# PowerDistribution.net
KiCad netlist of a schematic drawn in Altium Designer
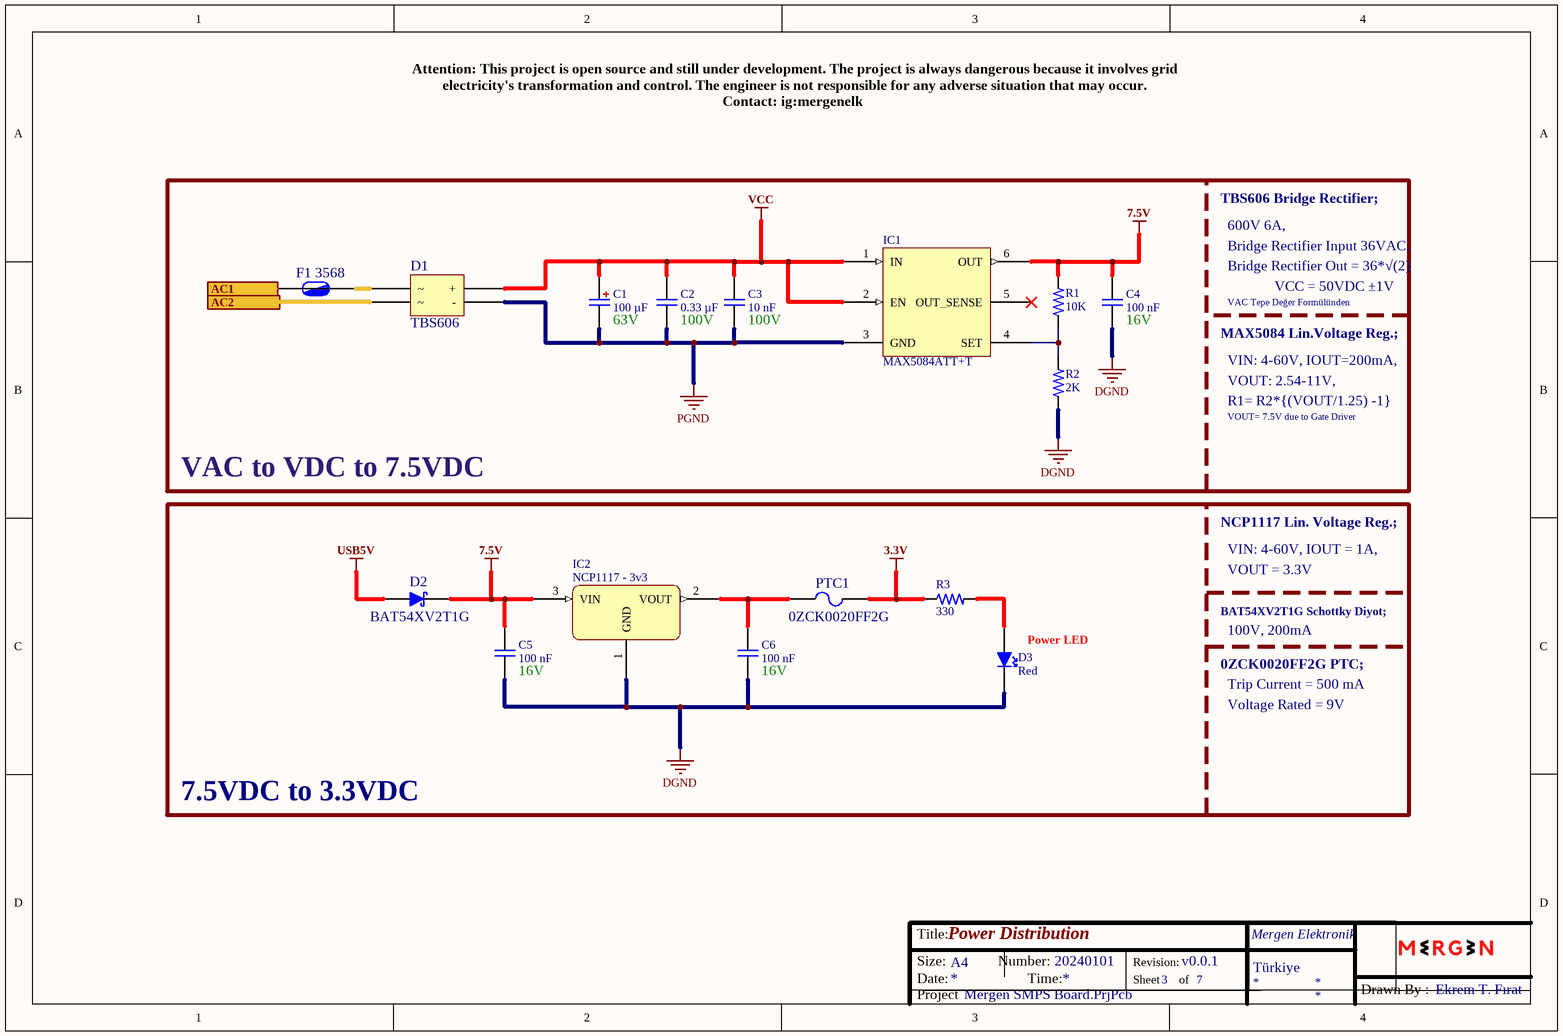
[diagram p0: PowerDistribution.SchDoc]

(export (version "E")
  (design (tool "Eeschema 10.0.6"))
  (components
    (comp (ref "C1")
      (value "100 µF")
      (footprint "MergenElektronik_Capacitors_AluminumElectrolytics_SMDs_10x10.5mm")
      (description "Mergen Elektronik - Capacitors - Aluminum Electrolytics - SMDs - UUX1J101MNL1GS")
      (fields
        (field (name "MANUFACTURER") "Nichicon")
        (field (name "TOLERANCE") "±20%")
        (field (name "VOLTAGE RATED") "63V")
      )
      (libsource (lib "MergenElektronik_Capacitors_AluminumElectrolytics_SMDs") (part "MergenElektronik_Capacitors_AluminumElectrolytics_SMDs_UUX1J101MNL1GS"))
    )
    (comp (ref "C2")
      (value "0.33 µF")
      (footprint "MergenElektronik_Capacitors_Ceramics_SMDs_1206_S_NS")
      (description "Mergen Elektronik - Capacitors - Ceramics - SMDs - 1206 - 0.33 µF - 100V")
      (fields
        (field (name "MANUFACTURER") "TDK Corporation")
        (field (name "TOLERANCE") "±10%")
        (field (name "VOLTAGE RATED") "100V")
      )
      (libsource (lib "MergenElektronik_Capacitors_Ceramics_SMDs") (part "MergenElektronik_Capacitors_Ceramic_SMDs_0.33µF_100V"))
    )
    (comp (ref "C3")
      (value "10 nF")
      (footprint "MergenElektronik_Capacitors_Ceramics_SMDs_0603_S_NS")
      (description "Mergen Elektronik - Capacitors - Ceramics - SMDs - 0603 - 10 nF - 100V")
      (fields
        (field (name "MANUFACTURER") "Murata Electronics")
        (field (name "TOLERANCE") "±10%")
        (field (name "VOLTAGE RATED") "100V")
      )
      (libsource (lib "MergenElektronik_Capacitors_Ceramics_SMDs") (part "MergenElektronik_Capacitors_Ceramic_SMDs_10nF_100V"))
    )
    (comp (ref "C4")
      (value "100 nF")
      (footprint "MergenElektronik_Capacitors_Ceramics_SMDs_0603_S_NS")
      (description "Mergen Elektronik - Capacitors - Ceramics - SMDs - 0603 - 100 nF - 16V")
      (fields
        (field (name "MANUFACTURER") "Samsung")
        (field (name "TOLERANCE") "±10%")
        (field (name "VOLTAGE RATED") "16V")
      )
      (libsource (lib "MergenElektronik_Capacitors_Ceramics_SMDs") (part "MergenElektronik_Capacitors_Ceramic_SMDs_100nF_16V"))
    )
    (comp (ref "C5")
      (value "100 nF")
      (footprint "MergenElektronik_Capacitors_Ceramics_SMDs_0603_S_NS")
      (description "Mergen Elektronik - Capacitors - Ceramics - SMDs - 0603 - 100 nF - 16V")
      (fields
        (field (name "MANUFACTURER") "Samsung")
        (field (name "TOLERANCE") "±10%")
        (field (name "VOLTAGE RATED") "16V")
      )
      (libsource (lib "MergenElektronik_Capacitors_Ceramics_SMDs") (part "MergenElektronik_Capacitors_Ceramic_SMDs_100nF_16V"))
    )
    (comp (ref "C6")
      (value "100 nF")
      (footprint "MergenElektronik_Capacitors_Ceramics_SMDs_0603_S_NS")
      (description "Mergen Elektronik - Capacitors - Ceramics - SMDs - 0603 - 100 nF - 16V")
      (fields
        (field (name "MANUFACTURER") "Samsung")
        (field (name "TOLERANCE") "±10%")
        (field (name "VOLTAGE RATED") "16V")
      )
      (libsource (lib "MergenElektronik_Capacitors_Ceramics_SMDs") (part "MergenElektronik_Capacitors_Ceramic_SMDs_100nF_16V"))
    )
    (comp (ref "D1")
      (value "TBS606")
      (footprint "MergenElektronik_Diodes_BridgeRectifiers_TBS606")
      (description "Mergen Elektronik - Diodes - Bridge Rectifiers - TBS606")
      (fields (field (name "MANUFACTURER") "Taiwan Semiconductor Corporation"))
      (libsource (lib "MergenElektronik_Diodes_BridgeRectifiers") (part "MergenElektronik_Diodes_BridgeRectifiers_TBS606"))
    )
    (comp (ref "D2")
      (value "BAT54XV2T1G")
      (footprint "MergenElektronik_Diodes_SchottkyDiodes_SOD-523")
      (description "Mergen Elektronik - Diodes - Schottky Diodes - BAT54XV2T1G")
      (fields (field (name "MANUFACTURER") "onsemi"))
      (libsource (lib "MergenElektronik_Diodes_SchottkyDiodes") (part "MergenElektronik_Diodes_SchottkyDiodes_BAT54XV2T1G"))
    )
    (comp (ref "D3")
      (value "Red")
      (footprint "MergenElektronik_Leds_SMDs_0603_S_NS")
      (description "Mergen Elektronik - Leds - SMDs - Red - 0603")
      (fields (field (name "MANUFACTURER") "Würth Elektronik"))
      (libsource (lib "MergenElektronik_Leds_SMDs") (part "MergenElektronik_LEDs_SMDs_Red_0603"))
    )
    (comp (ref "F1")
      (value "3568")
      (footprint "MergenElektronik_FuseHolders_BladeType_3568")
      (description "Mergen Elektronik - Fuse Holder - Blade Type - 3568")
      (fields (field (name "MANUFACTURER") "Keystone"))
      (libsource (lib "MergenElektronik_FuseHolders_BladeType") (part "MergenElektronik_FuseHolders_BladeType_3568"))
    )
    (comp (ref "IC1")
      (value "MAX5084ATT+T")
      (footprint "MergenElektronik_Regulators_Linears_6-TDFN")
      (description "Mergen Elektronik - Regulators - Linears - MAX5084ATT+T")
      (fields (field (name "MANUFACTURER") "Analog Devices Inc./Maxim Integrated"))
      (libsource (lib "MergenElektronik_Regulators_Linears") (part "MergenElektronik_Regulators_Linears_MAX5084ATT+T"))
    )
    (comp (ref "IC2")
      (value "NCP1117 - 3v3")
      (footprint "MergenElektronik_Regulators_Linears_SOT223")
      (description "Mergen Elektronik - Regulators - Linears - NCP1117ST33T3G")
      (fields (field (name "MANUFACTURER") "onsemi"))
      (libsource (lib "MergenElektronik_Regulators_Linears") (part "MergenElektronik_Regulators_Linears_NCP1117ST33T3G"))
    )
    (comp (ref "PTC1")
      (value "0ZCK0020FF2G")
      (footprint "MergenElektronik_CircuitProtections_PTCs_0603_S_NS")
      (description "Mergen Elektronik - Circuit Protections - PTCs - 0ZCK0020FF2G")
      (fields (field (name "MANUFACTURER") "Bel Fuse"))
      (libsource (lib "MergenElektronik_CircuitProtections_PTCs") (part "MergenElektronik_CircuitProtections_PTCs_0ZCK0020FF2G"))
    )
    (comp (ref "R1")
      (value "10K")
      (footprint "MergenElektronik_Resistors_ChipResistors_0603_S_NS")
      (description "Mergen Elektronik - Resistors - Chip Resistors - 0603 - 10K")
      (fields (field (name "MANUFACTURER") "Stackpole") (field (name "POWER") "1/10W"))
      (libsource (lib "MergenElektronik_Resistors_ChipResistors") (part "MergenElektronik_Resistors_ChipResistors_0603_10K"))
    )
    (comp (ref "R2")
      (value "2K")
      (footprint "MergenElektronik_Resistors_ChipResistors_0603_S_NS")
      (description "Mergen Elektronik - Resistors - Chip Resistors - 0603 - 2K")
      (fields (field (name "MANUFACTURER") "Panasonix") (field (name "POWER") "1/10W"))
      (libsource (lib "MergenElektronik_Resistors_ChipResistors") (part "MergenElektronik_Resistors_ChipResistors_0603_2K"))
    )
    (comp (ref "R3")
      (value "330")
      (footprint "MergenElektronik_Resistors_ChipResistors_0603_S_NS")
      (description "Mergen Elektronik - Resistors - Chip Resistors - 0603 - 330R")
      (fields (field (name "MANUFACTURER") "Stackpole") (field (name "POWER") "1/10W"))
      (libsource (lib "MergenElektronik_Resistors_ChipResistors") (part "MergenElektronik_Resistors_ChipResistors_0603_330R"))
    )
  )
  (nets
    (net (code "2") (name "/AC2") (class "Default")
      (node (ref "D1") (pin "4") (pinfunction "~_4") (pintype "power_in"))
    )
    (net (code "3") (name "3.3V") (class "Default")
      (node (ref "PTC1") (pin "2") (pinfunction "2_2") (pintype "passive"))
      (node (ref "R3") (pin "1") (pinfunction "1_1") (pintype "passive"))
    )
    (net (code "4") (name "7.5V") (class "Default")
      (node (ref "C4") (pin "1") (pinfunction "1_1") (pintype "passive"))
      (node (ref "C5") (pin "1") (pinfunction "1_1") (pintype "passive"))
      (node (ref "D2") (pin "2") (pinfunction "KATOT_2") (pintype "passive"))
      (node (ref "IC1") (pin "6") (pinfunction "OUT_6") (pintype "output"))
      (node (ref "IC2") (pin "3") (pinfunction "VIN_3") (pintype "input"))
      (node (ref "R1") (pin "2") (pinfunction "2_2") (pintype "passive"))
    )
    (net (code "5") (name "DGND") (class "Default")
      (node (ref "C4") (pin "2") (pinfunction "2_2") (pintype "passive"))
      (node (ref "C5") (pin "2") (pinfunction "2_2") (pintype "passive"))
      (node (ref "C6") (pin "2") (pinfunction "2_2") (pintype "passive"))
      (node (ref "D3") (pin "2") (pinfunction "KATOT_2") (pintype "passive"))
      (node (ref "IC2") (pin "1") (pinfunction "GND_1") (pintype "power_in"))
      (node (ref "R2") (pin "1") (pinfunction "1_1") (pintype "passive"))
    )
    (net (code "6") (name "Net-(D1-~-Pad3)") (class "Default")
      (node (ref "D1") (pin "3") (pinfunction "~_3") (pintype "power_in"))
      (node (ref "F1") (pin "2") (pinfunction "2_2") (pintype "passive"))
    )
    (net (code "7") (name "Net-(D3-ANOT)") (class "Default")
      (node (ref "D3") (pin "1") (pinfunction "ANOT_1") (pintype "passive"))
      (node (ref "R3") (pin "2") (pinfunction "2_2") (pintype "passive"))
    )
    (net (code "8") (name "Net-(IC1-SET)") (class "Default")
      (node (ref "IC1") (pin "4") (pinfunction "SET_4") (pintype "passive"))
      (node (ref "R1") (pin "1") (pinfunction "1_1") (pintype "passive"))
      (node (ref "R2") (pin "2") (pinfunction "2_2") (pintype "passive"))
    )
    (net (code "9") (name "Net-(IC2-VOUT)") (class "Default")
      (node (ref "C6") (pin "1") (pinfunction "1_1") (pintype "passive"))
      (node (ref "IC2") (pin "2") (pinfunction "VOUT_2") (pintype "output"))
      (node (ref "PTC1") (pin "1") (pinfunction "1_1") (pintype "passive"))
    )
    (net (code "10") (name "PGND") (class "Default")
      (node (ref "C1") (pin "1") (pinfunction "1_1") (pintype "passive"))
      (node (ref "C2") (pin "2") (pinfunction "2_2") (pintype "passive"))
      (node (ref "C3") (pin "2") (pinfunction "2_2") (pintype "passive"))
      (node (ref "D1") (pin "2") (pinfunction "-_2") (pintype "power_in"))
      (node (ref "IC1") (pin "3") (pinfunction "GND_3") (pintype "power_in"))
    )
    (net (code "11") (name "USB5V") (class "Default")
      (node (ref "D2") (pin "1") (pinfunction "ANOT_1") (pintype "passive"))
    )
    (net (code "12") (name "VCC") (class "Default")
      (node (ref "C1") (pin "2") (pinfunction "2_2") (pintype "passive"))
      (node (ref "C2") (pin "1") (pinfunction "1_1") (pintype "passive"))
      (node (ref "C3") (pin "1") (pinfunction "1_1") (pintype "passive"))
      (node (ref "D1") (pin "1") (pinfunction "+_1") (pintype "power_in"))
      (node (ref "IC1") (pin "1") (pinfunction "IN_1") (pintype "input"))
      (node (ref "IC1") (pin "2") (pinfunction "EN_2") (pintype "input"))
    )
    (net (code "13") (name "unconnected-(F1-Pad1)") (class "Default")
      (node (ref "F1") (pin "1") (pinfunction "1_1") (pintype "passive"))
    )
    (net (code "14") (name "unconnected-(IC1-OUT_SENSE-Pad5)") (class "Default")
      (node (ref "IC1") (pin "5") (pinfunction "OUT_SENSE_5") (pintype "passive+no_connect"))
    )
  )
)
